# Sine.net
KiCad netlist of a schematic drawn in Altium Designer
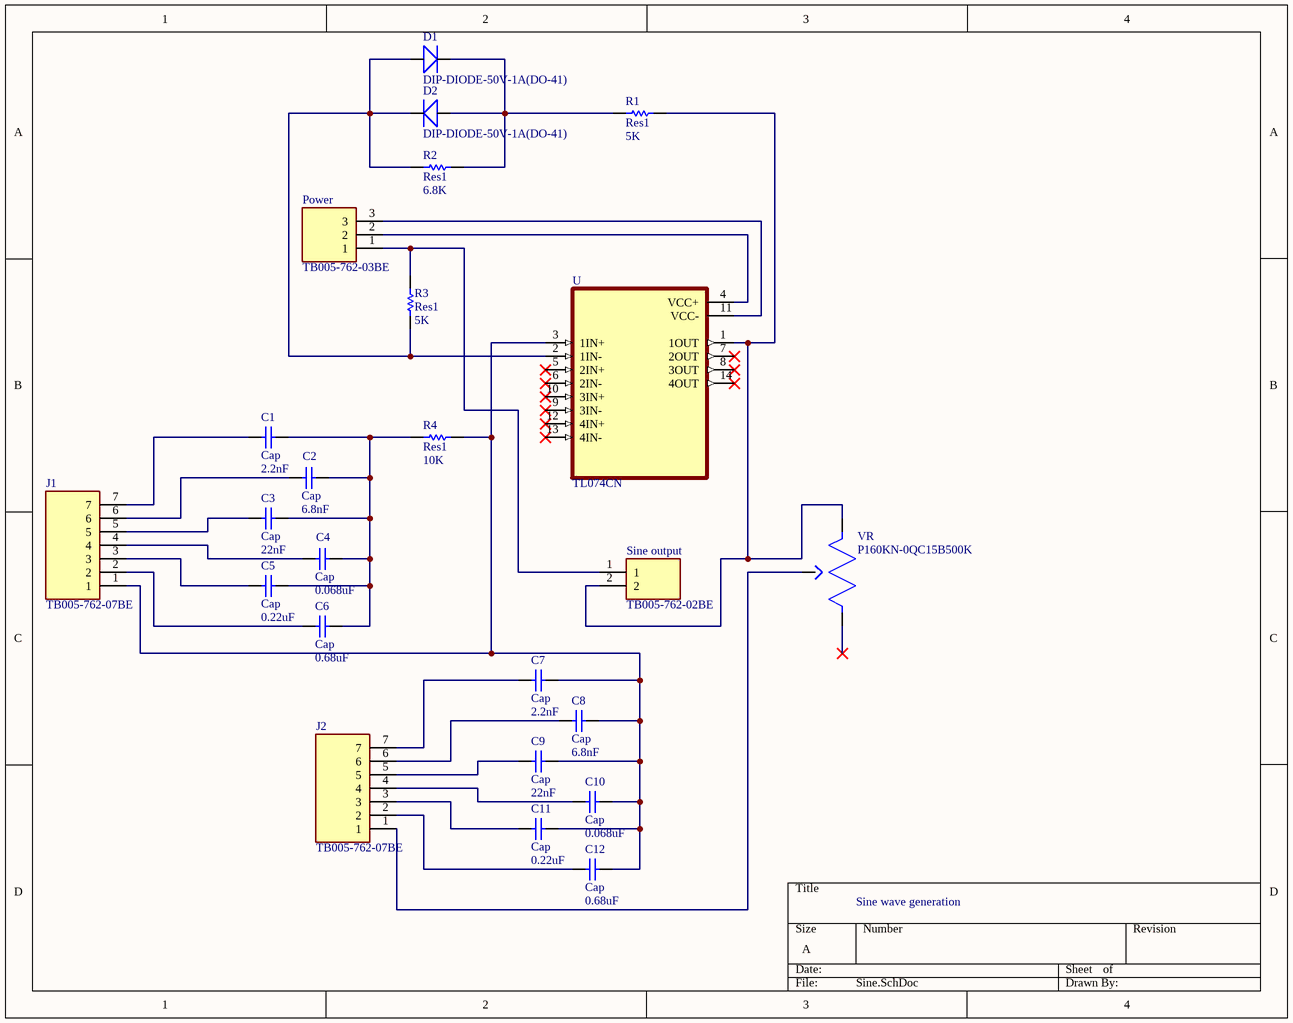
[diagram p0: Sine.SchDoc]

(export (version "E")
  (design (tool "Eeschema 10.0.6"))
  (components
    (comp (ref "C1")
      (value "Cap")
      (footprint "RAD-0.3")
      (description "Capacitor")
      (fields (field (name "ALTIUM_VALUE") "2.2nF") (field (name "PUBLISHER") "Altium Limited"))
      (libsource (lib "Miscellaneous Devices") (part "Cap"))
    )
    (comp (ref "C2")
      (value "Cap")
      (footprint "RAD-0.3")
      (description "Capacitor")
      (fields (field (name "ALTIUM_VALUE") "6.8nF") (field (name "PUBLISHER") "Altium Limited"))
      (libsource (lib "Miscellaneous Devices") (part "Cap"))
    )
    (comp (ref "C3")
      (value "Cap")
      (footprint "RAD-0.3")
      (description "Capacitor")
      (fields (field (name "ALTIUM_VALUE") "22nF") (field (name "PUBLISHER") "Altium Limited"))
      (libsource (lib "Miscellaneous Devices") (part "Cap"))
    )
    (comp (ref "C4")
      (value "Cap")
      (footprint "RAD-0.3")
      (description "Capacitor")
      (fields (field (name "ALTIUM_VALUE") "0.068uF") (field (name "PUBLISHER") "Altium Limited"))
      (libsource (lib "Miscellaneous Devices") (part "Cap"))
    )
    (comp (ref "C5")
      (value "Cap")
      (footprint "RAD-0.3")
      (description "Capacitor")
      (fields (field (name "ALTIUM_VALUE") "0.22uF") (field (name "PUBLISHER") "Altium Limited"))
      (libsource (lib "Miscellaneous Devices") (part "Cap"))
    )
    (comp (ref "C6")
      (value "Cap")
      (footprint "RAD-0.3")
      (description "Capacitor")
      (fields (field (name "ALTIUM_VALUE") "0.68uF") (field (name "PUBLISHER") "Altium Limited"))
      (libsource (lib "Miscellaneous Devices") (part "Cap"))
    )
    (comp (ref "C7")
      (value "Cap")
      (footprint "RAD-0.3")
      (description "Capacitor")
      (fields (field (name "ALTIUM_VALUE") "2.2nF") (field (name "PUBLISHER") "Altium Limited"))
      (libsource (lib "Miscellaneous Devices") (part "Cap"))
    )
    (comp (ref "C8")
      (value "Cap")
      (footprint "RAD-0.3")
      (description "Capacitor")
      (fields (field (name "ALTIUM_VALUE") "6.8nF") (field (name "PUBLISHER") "Altium Limited"))
      (libsource (lib "Miscellaneous Devices") (part "Cap"))
    )
    (comp (ref "C9")
      (value "Cap")
      (footprint "RAD-0.3")
      (description "Capacitor")
      (fields (field (name "ALTIUM_VALUE") "22nF") (field (name "PUBLISHER") "Altium Limited"))
      (libsource (lib "Miscellaneous Devices") (part "Cap"))
    )
    (comp (ref "C10")
      (value "Cap")
      (footprint "RAD-0.3")
      (description "Capacitor")
      (fields (field (name "ALTIUM_VALUE") "0.068uF") (field (name "PUBLISHER") "Altium Limited"))
      (libsource (lib "Miscellaneous Devices") (part "Cap"))
    )
    (comp (ref "C11")
      (value "Cap")
      (footprint "RAD-0.3")
      (description "Capacitor")
      (fields (field (name "ALTIUM_VALUE") "0.22uF") (field (name "PUBLISHER") "Altium Limited"))
      (libsource (lib "Miscellaneous Devices") (part "Cap"))
    )
    (comp (ref "C12")
      (value "Cap")
      (footprint "RAD-0.3")
      (description "Capacitor")
      (fields (field (name "ALTIUM_VALUE") "0.68uF") (field (name "PUBLISHER") "Altium Limited"))
      (libsource (lib "Miscellaneous Devices") (part "Cap"))
    )
    (comp (ref "D1")
      (value "DIP-DIODE-50V-1A(DO-41)")
      (footprint "DO-41")
      (description "Diode Standard 50V 1A Through Hole DO-41")
      (fields (field (name "MF") "Comchip Technology") (field (name "MP") "1N4001-G"))
      (libsource (lib "DIP-DIODE-50V-1A_DO-41_") (part "DIP-DIODE-50V-1A(DO-41)"))
    )
    (comp (ref "D2")
      (value "DIP-DIODE-50V-1A(DO-41)")
      (footprint "DO-41")
      (description "Diode Standard 50V 1A Through Hole DO-41")
      (fields (field (name "MF") "Comchip Technology") (field (name "MP") "1N4001-G"))
      (libsource (lib "DIP-DIODE-50V-1A_DO-41_") (part "DIP-DIODE-50V-1A(DO-41)"))
    )
    (comp (ref "J1")
      (value "TB005-762-07BE")
      (footprint "CUI_TB005-762-07BE")
      (description "2~24 Poles, Screw Type, Horizontal, 7.62 Pitch, 26~10 (AWG), Terminal Block Connector")
      (fields (field (name "MF") "CUI Devices"))
      (libsource (lib "TB005-762-07BE") (part "TB005-762-07BE"))
    )
    (comp (ref "J2")
      (value "TB005-762-07BE")
      (footprint "CUI_TB005-762-07BE")
      (description "2~24 Poles, Screw Type, Horizontal, 7.62 Pitch, 26~10 (AWG), Terminal Block Connector")
      (fields (field (name "MF") "CUI Devices"))
      (libsource (lib "TB005-762-07BE") (part "TB005-762-07BE"))
    )
    (comp (ref "Power")
      (value "TB005-762-03BE")
      (footprint "CUI_TB005-762-03BE")
      (description "2~24 Poles, Screw Type, Horizontal, 7.62 Pitch, 26~10 _AWG_, Terminal Block Connector")
      (fields (field (name "MF") "CUI Devices"))
      (libsource (lib "TB005-762-03BE") (part "TB005-762-03BE"))
    )
    (comp (ref "R1")
      (value "Res1")
      (footprint "AXIAL-0.3")
      (description "Resistor")
      (fields (field (name "ALTIUM_VALUE") "5K") (field (name "PUBLISHER") "Altium Limited"))
      (libsource (lib "Miscellaneous Devices") (part "Res1"))
    )
    (comp (ref "R2")
      (value "Res1")
      (footprint "AXIAL-0.3")
      (description "Resistor")
      (fields (field (name "ALTIUM_VALUE") "6.8K") (field (name "PUBLISHER") "Altium Limited"))
      (libsource (lib "Miscellaneous Devices") (part "Res1"))
    )
    (comp (ref "R3")
      (value "Res1")
      (footprint "AXIAL-0.3")
      (description "Resistor")
      (fields (field (name "ALTIUM_VALUE") "5K") (field (name "PUBLISHER") "Altium Limited"))
      (libsource (lib "Miscellaneous Devices") (part "Res1"))
    )
    (comp (ref "R4")
      (value "Res1")
      (footprint "AXIAL-0.3")
      (description "Resistor")
      (fields (field (name "ALTIUM_VALUE") "10K") (field (name "PUBLISHER") "Altium Limited"))
      (libsource (lib "Miscellaneous Devices") (part "Res1"))
    )
    (comp (ref "Sine output")
      (value "TB005-762-02BE")
      (footprint "CUI_TB005-762-02BE")
      (description "2~24 Poles, Screw Type, Horizontal, 7.62 Pitch, 26~10 _AWG_, Terminal Block Connector")
      (fields (field (name "MF") "CUI Devices"))
      (libsource (lib "TB005-762-02BE") (part "TB005-762-02BE"))
    )
    (comp (ref "U")
      (value "TL074CN")
      (footprint "DIP794W45P254L1969H508Q14")
      (description "Quad Low-Noise JFET-Input General-Purpose Operational Amplifier 14-PDIP 0 to 70")
      (fields (field (name "MF") "Texas Instruments"))
      (libsource (lib "TL074CN") (part "TL074CN"))
    )
    (comp (ref "VR")
      (value "P160KN-0QC15B500K")
      (footprint "P160")
      (description "500k Ohm 1 Gang Linear Panel Mount Potentiometer None 1 Turn Conductive Plastic 0.2W, 1/5W PC Pins")
      (fields (field (name "MF") "TT Electronics/BI") (field (name "DIGI-KEY_PART_NUMBER") "987-1304-ND"))
      (libsource (lib "P160KN-0QC15B500K") (part "P160KN-0QC15B500K"))
    )
  )
  (nets
    (net (code "1") (name "Net-(C1-Pad1)") (class "Default")
      (node (ref "C1") (pin "1") (pinfunction "1_1") (pintype "passive"))
      (node (ref "J1") (pin "7") (pinfunction "7_7") (pintype "passive"))
    )
    (net (code "2") (name "Net-(C1-Pad2)") (class "Default")
      (node (ref "C1") (pin "2") (pinfunction "2_2") (pintype "passive"))
      (node (ref "C2") (pin "2") (pinfunction "2_2") (pintype "passive"))
      (node (ref "C3") (pin "2") (pinfunction "2_2") (pintype "passive"))
      (node (ref "C4") (pin "2") (pinfunction "2_2") (pintype "passive"))
      (node (ref "C5") (pin "2") (pinfunction "2_2") (pintype "passive"))
      (node (ref "C6") (pin "2") (pinfunction "2_2") (pintype "passive"))
      (node (ref "R4") (pin "1") (pinfunction "1_1") (pintype "passive"))
    )
    (net (code "3") (name "Net-(C2-Pad1)") (class "Default")
      (node (ref "C2") (pin "1") (pinfunction "1_1") (pintype "passive"))
      (node (ref "J1") (pin "6") (pinfunction "6_6") (pintype "passive"))
    )
    (net (code "4") (name "Net-(C3-Pad1)") (class "Default")
      (node (ref "C3") (pin "1") (pinfunction "1_1") (pintype "passive"))
      (node (ref "J1") (pin "5") (pinfunction "5_5") (pintype "passive"))
    )
    (net (code "5") (name "Net-(C4-Pad1)") (class "Default")
      (node (ref "C4") (pin "1") (pinfunction "1_1") (pintype "passive"))
      (node (ref "J1") (pin "4") (pinfunction "4_4") (pintype "passive"))
    )
    (net (code "6") (name "Net-(C5-Pad1)") (class "Default")
      (node (ref "C5") (pin "1") (pinfunction "1_1") (pintype "passive"))
      (node (ref "J1") (pin "3") (pinfunction "3_3") (pintype "passive"))
    )
    (net (code "7") (name "Net-(C6-Pad1)") (class "Default")
      (node (ref "C6") (pin "1") (pinfunction "1_1") (pintype "passive"))
      (node (ref "J1") (pin "2") (pinfunction "2_2") (pintype "passive"))
    )
    (net (code "8") (name "Net-(C7-Pad1)") (class "Default")
      (node (ref "C7") (pin "1") (pinfunction "1_1") (pintype "passive"))
      (node (ref "J2") (pin "7") (pinfunction "7_7") (pintype "passive"))
    )
    (net (code "9") (name "Net-(C8-Pad1)") (class "Default")
      (node (ref "C8") (pin "1") (pinfunction "1_1") (pintype "passive"))
      (node (ref "J2") (pin "6") (pinfunction "6_6") (pintype "passive"))
    )
    (net (code "10") (name "Net-(C9-Pad1)") (class "Default")
      (node (ref "C9") (pin "1") (pinfunction "1_1") (pintype "passive"))
      (node (ref "J2") (pin "5") (pinfunction "5_5") (pintype "passive"))
    )
    (net (code "11") (name "Net-(C10-Pad1)") (class "Default")
      (node (ref "C10") (pin "1") (pinfunction "1_1") (pintype "passive"))
      (node (ref "J2") (pin "4") (pinfunction "4_4") (pintype "passive"))
    )
    (net (code "12") (name "Net-(C11-Pad1)") (class "Default")
      (node (ref "C11") (pin "1") (pinfunction "1_1") (pintype "passive"))
      (node (ref "J2") (pin "3") (pinfunction "3_3") (pintype "passive"))
    )
    (net (code "13") (name "Net-(C12-Pad1)") (class "Default")
      (node (ref "C12") (pin "1") (pinfunction "1_1") (pintype "passive"))
      (node (ref "J2") (pin "2") (pinfunction "2_2") (pintype "passive"))
    )
    (net (code "14") (name "Net-(D1-NEG)") (class "Default")
      (node (ref "D1") (pin "2") (pinfunction "NEG_2") (pintype "passive"))
      (node (ref "D2") (pin "1") (pinfunction "POS_1") (pintype "passive"))
      (node (ref "R1") (pin "1") (pinfunction "1_1") (pintype "passive"))
      (node (ref "R2") (pin "2") (pinfunction "2_2") (pintype "passive"))
    )
    (net (code "15") (name "Net-(D1-POS)") (class "Default")
      (node (ref "D1") (pin "1") (pinfunction "POS_1") (pintype "passive"))
      (node (ref "D2") (pin "2") (pinfunction "NEG_2") (pintype "passive"))
      (node (ref "R2") (pin "1") (pinfunction "1_1") (pintype "passive"))
      (node (ref "R3") (pin "1") (pinfunction "1_1") (pintype "passive"))
      (node (ref "U") (pin "2") (pinfunction "1IN-_2") (pintype "input"))
    )
    (net (code "16") (name "Net-(J2-Pad1)") (class "Default")
      (node (ref "J2") (pin "1") (pinfunction "1_1") (pintype "passive"))
      (node (ref "VR") (pin "2") (pinfunction "2_2") (pintype "bidirectional"))
    )
    (net (code "17") (name "Net-(Power-Pad1)") (class "Default")
      (node (ref "Power") (pin "1") (pinfunction "1_1") (pintype "passive"))
      (node (ref "R3") (pin "2") (pinfunction "2_2") (pintype "passive"))
      (node (ref "Sine output") (pin "1") (pinfunction "1_1") (pintype "passive"))
    )
    (net (code "18") (name "Net-(U-1IN+)") (class "Default")
      (node (ref "C10") (pin "2") (pinfunction "2_2") (pintype "passive"))
      (node (ref "C11") (pin "2") (pinfunction "2_2") (pintype "passive"))
      (node (ref "C12") (pin "2") (pinfunction "2_2") (pintype "passive"))
      (node (ref "C7") (pin "2") (pinfunction "2_2") (pintype "passive"))
      (node (ref "C8") (pin "2") (pinfunction "2_2") (pintype "passive"))
      (node (ref "C9") (pin "2") (pinfunction "2_2") (pintype "passive"))
      (node (ref "J1") (pin "1") (pinfunction "1_1") (pintype "passive"))
      (node (ref "R4") (pin "2") (pinfunction "2_2") (pintype "passive"))
      (node (ref "U") (pin "3") (pinfunction "1IN+_3") (pintype "input"))
    )
    (net (code "19") (name "Net-(U-1OUT)") (class "Default")
      (node (ref "R1") (pin "2") (pinfunction "2_2") (pintype "passive"))
      (node (ref "Sine output") (pin "2") (pinfunction "2_2") (pintype "passive"))
      (node (ref "U") (pin "1") (pinfunction "1OUT_1") (pintype "output"))
      (node (ref "VR") (pin "1") (pinfunction "1_1") (pintype "bidirectional"))
    )
    (net (code "20") (name "Net-(U-VCC+)") (class "Default")
      (node (ref "Power") (pin "2") (pinfunction "2_2") (pintype "passive"))
      (node (ref "U") (pin "4") (pinfunction "VCC+_4") (pintype "power_in"))
    )
    (net (code "21") (name "Net-(U-VCC-)") (class "Default")
      (node (ref "Power") (pin "3") (pinfunction "3_3") (pintype "passive"))
      (node (ref "U") (pin "11") (pinfunction "VCC-_11") (pintype "power_in"))
    )
    (net (code "22") (name "unconnected-(U-2IN+-Pad5)") (class "Default")
      (node (ref "U") (pin "5") (pinfunction "2IN+_5") (pintype "input+no_connect"))
    )
    (net (code "23") (name "unconnected-(U-2IN--Pad6)") (class "Default")
      (node (ref "U") (pin "6") (pinfunction "2IN-_6") (pintype "input+no_connect"))
    )
    (net (code "24") (name "unconnected-(U-2OUT-Pad7)") (class "Default")
      (node (ref "U") (pin "7") (pinfunction "2OUT_7") (pintype "output+no_connect"))
    )
    (net (code "25") (name "unconnected-(U-3IN+-Pad10)") (class "Default")
      (node (ref "U") (pin "10") (pinfunction "3IN+_10") (pintype "input+no_connect"))
    )
    (net (code "26") (name "unconnected-(U-3IN--Pad9)") (class "Default")
      (node (ref "U") (pin "9") (pinfunction "3IN-_9") (pintype "input+no_connect"))
    )
    (net (code "27") (name "unconnected-(U-3OUT-Pad8)") (class "Default")
      (node (ref "U") (pin "8") (pinfunction "3OUT_8") (pintype "output+no_connect"))
    )
    (net (code "28") (name "unconnected-(U-4IN+-Pad12)") (class "Default")
      (node (ref "U") (pin "12") (pinfunction "4IN+_12") (pintype "input+no_connect"))
    )
    (net (code "29") (name "unconnected-(U-4IN--Pad13)") (class "Default")
      (node (ref "U") (pin "13") (pinfunction "4IN-_13") (pintype "input+no_connect"))
    )
    (net (code "30") (name "unconnected-(U-4OUT-Pad14)") (class "Default")
      (node (ref "U") (pin "14") (pinfunction "4OUT_14") (pintype "output+no_connect"))
    )
    (net (code "31") (name "unconnected-(VR-Pad3)") (class "Default")
      (node (ref "VR") (pin "3") (pinfunction "3_3") (pintype "bidirectional+no_connect"))
    )
  )
)
